# HV_power.net
KiCad netlist of a schematic drawn in Altium Designer
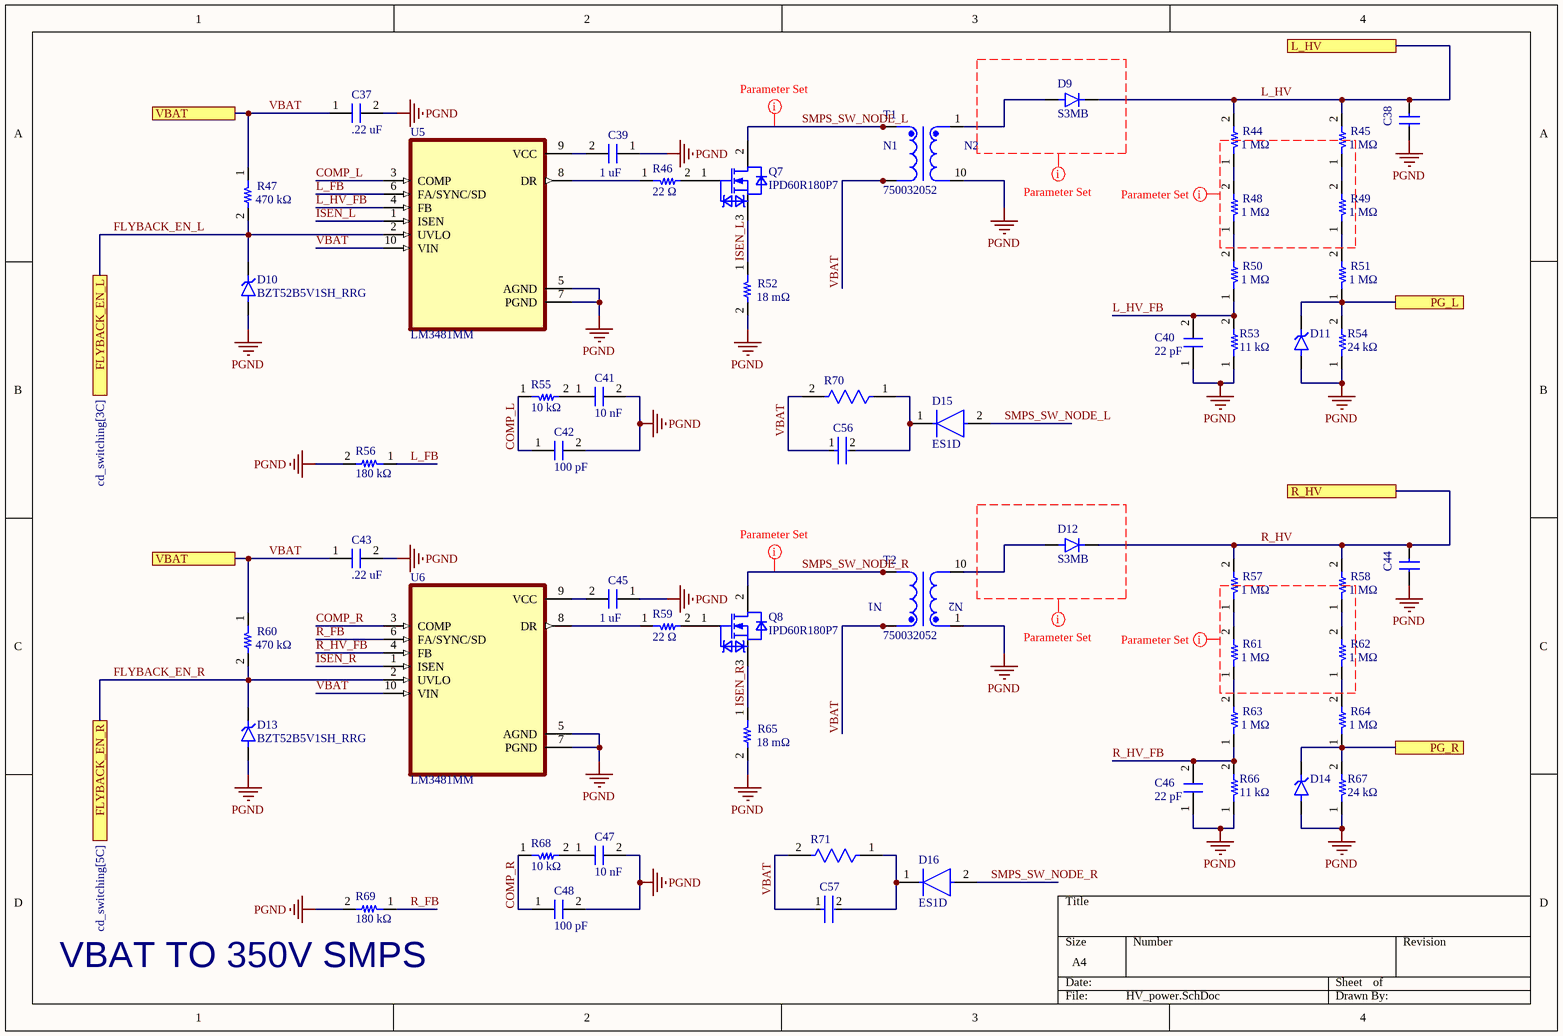
[diagram p0: HV_power.SchDoc]

(export (version "E")
  (design (tool "Eeschema 10.0.6"))
  (components
    (comp (ref "C37")
      (value ".22 uF")
      (footprint "0603_FP")
      (fields (field (name "Comment") "GRM21BR61C475KA88L"))
      (libsource (lib "RC_sch") (part "Capacitor_0603"))
    )
    (comp (ref "C38")
      (value "WCAP-FTBP_P10")
      (footprint "WCAP-FTBP_10X13X5.5X11(PXLXWXH)")
      (fields (field (name "MF") "Wurth Elektronik") (field (name "MP") "890283323005CS"))
      (libsource (lib "WCAP-FTBP_P10") (part "WCAP-FTBP_P10"))
    )
    (comp (ref "C39")
      (value "1 uF")
      (footprint "0603_FP")
      (fields (field (name "Comment") "Capacitor_0603"))
      (libsource (lib "RC_sch") (part "Capacitor_0603"))
    )
    (comp (ref "C40")
      (value "22 pF")
      (footprint "0603_FP")
      (fields (field (name "Comment") "Capacitor_0603"))
      (libsource (lib "RC_sch") (part "Capacitor_0603"))
    )
    (comp (ref "C41")
      (value "10 nF")
      (footprint "0603_FP")
      (fields (field (name "Comment") "Capacitor_0603"))
      (libsource (lib "RC_sch") (part "Capacitor_0603"))
    )
    (comp (ref "C42")
      (value "100 pF")
      (footprint "0603_FP")
      (fields (field (name "Comment") "Capacitor_0603"))
      (libsource (lib "RC_sch") (part "Capacitor_0603"))
    )
    (comp (ref "C43")
      (value ".22 uF")
      (footprint "0603_FP")
      (fields (field (name "Comment") "GRM21BR61C475KA88L"))
      (libsource (lib "RC_sch") (part "Capacitor_0603"))
    )
    (comp (ref "C44")
      (value "WCAP-FTBP_P10")
      (footprint "WCAP-FTBP_10X13X5.5X11(PXLXWXH)")
      (fields (field (name "MF") "Wurth Elektronik") (field (name "MP") "890283323005CS"))
      (libsource (lib "WCAP-FTBP_P10") (part "WCAP-FTBP_P10"))
    )
    (comp (ref "C45")
      (value "1 uF")
      (footprint "0603_FP")
      (fields (field (name "Comment") "Capacitor_0603"))
      (libsource (lib "RC_sch") (part "Capacitor_0603"))
    )
    (comp (ref "C46")
      (value "22 pF")
      (footprint "0603_FP")
      (fields (field (name "Comment") "Capacitor_0603"))
      (libsource (lib "RC_sch") (part "Capacitor_0603"))
    )
    (comp (ref "C47")
      (value "10 nF")
      (footprint "0603_FP")
      (fields (field (name "Comment") "Capacitor_0603"))
      (libsource (lib "RC_sch") (part "Capacitor_0603"))
    )
    (comp (ref "C48")
      (value "100 pF")
      (footprint "0603_FP")
      (fields (field (name "Comment") "Capacitor_0603"))
      (libsource (lib "RC_sch") (part "Capacitor_0603"))
    )
    (comp (ref "C56")
      (value "C1206C683K1RACAUTO")
      (footprint "FP-C1206C-EB-MFG")
      (description "C1206 68,000 pF X7R 10.00% 100 V")
      (fields
        (field (name "MANUFACTURER") "KEMET")
        (field (name "OCTOPART") "https://octopart.com/c1206c683k1racauto-kemet-89187447")
      )
      (libsource (lib "Altium Content Vault") (part "b4654b650e69147ec39a6b967a45e02"))
    )
    (comp (ref "C57")
      (value "C1206C683K1RACAUTO")
      (footprint "FP-C1206C-EB-MFG")
      (description "C1206 68,000 pF X7R 10.00% 100 V")
      (fields
        (field (name "MANUFACTURER") "KEMET")
        (field (name "OCTOPART") "https://octopart.com/c1206c683k1racauto-kemet-89187447")
      )
      (libsource (lib "Altium Content Vault") (part "b4654b650e69147ec39a6b967a45e02"))
    )
    (comp (ref "D9")
      (value "S3MB")
      (footprint "DIOM4336X265N")
      (description "3A, 1000V, Standard Recovery Rectifier")
      (fields (field (name "MF") "Taiwan Semiconductor"))
      (libsource (lib "S3MB") (part "S3MB"))
    )
    (comp (ref "D10")
      (value "BZT52B5V1SH_RRG")
      (footprint "DIO_BZT52B5V1SH_RRG")
      (description "SOD-323, 200mW, 2%, 5.1V, Zener Diode")
      (fields (field (name "MF") "Taiwan Semiconductor Corporation") (field (name "MP") "BZT52B5V1SH RRG"))
      (libsource (lib "BZT52B5V1SH_RRG") (part "BZT52B5V1SH_RRG"))
    )
    (comp (ref "D11")
      (value "BZT52B15SH_RRG")
      (footprint "DIO_BZT52B15SH_RRG")
      (description "SOD-323, 200mW, 2%, 15V, Zener Diode")
      (fields (field (name "MF") "Taiwan Semiconductor Corporation") (field (name "MP") "BZT52B15SH RRG"))
      (libsource (lib "BZT52B15SH_RRG") (part "BZT52B15SH_RRG"))
    )
    (comp (ref "D12")
      (value "S3MB")
      (footprint "DIOM4336X265N")
      (description "3A, 1000V, Standard Recovery Rectifier")
      (fields (field (name "MF") "Taiwan Semiconductor"))
      (libsource (lib "S3MB") (part "S3MB"))
    )
    (comp (ref "D13")
      (value "BZT52B5V1SH_RRG")
      (footprint "DIO_BZT52B5V1SH_RRG")
      (description "SOD-323, 200mW, 2%, 5.1V, Zener Diode")
      (fields (field (name "MF") "Taiwan Semiconductor Corporation") (field (name "MP") "BZT52B5V1SH RRG"))
      (libsource (lib "BZT52B5V1SH_RRG") (part "BZT52B5V1SH_RRG"))
    )
    (comp (ref "D14")
      (value "BZT52B15SH_RRG")
      (footprint "DIO_BZT52B15SH_RRG")
      (description "SOD-323, 200mW, 2%, 15V, Zener Diode")
      (fields (field (name "MF") "Taiwan Semiconductor Corporation") (field (name "MP") "BZT52B15SH RRG"))
      (libsource (lib "BZT52B15SH_RRG") (part "BZT52B15SH_RRG"))
    )
    (comp (ref "D15")
      (value "ES1D")
      (footprint "FP-403AE-MFG")
      (description "Diode Switching 200V 1A 2-Pin SMA T/R")
      (fields (field (name "MANUFACTURER") "ON Semi"))
      (libsource (lib "Altium Content Vault") (part "d7152d700b627762746794eb795d46e"))
    )
    (comp (ref "D16")
      (value "ES1D")
      (footprint "FP-403AE-MFG")
      (description "Diode Switching 200V 1A 2-Pin SMA T/R")
      (fields (field (name "MANUFACTURER") "ON Semi"))
      (libsource (lib "Altium Content Vault") (part "d7152d700b627762746794eb795d46e"))
    )
    (comp (ref "Q7")
      (value "IPD60R180P7")
      (footprint "DPAK228P987X240-3N")
      (fields (field (name "MANUFACTURER") "Infineon Technologies"))
      (libsource (lib "IPD60R180P7") (part "IPD60R180P7"))
    )
    (comp (ref "Q8")
      (value "IPD60R180P7")
      (footprint "DPAK228P987X240-3N")
      (fields (field (name "MANUFACTURER") "Infineon Technologies"))
      (libsource (lib "IPD60R180P7") (part "IPD60R180P7"))
    )
    (comp (ref "R44")
      (value "1 MΩ")
      (footprint "0805_FP")
      (fields (field (name "Comment") "R_0805"))
      (libsource (lib "0805_R") (part "R_0805"))
    )
    (comp (ref "R45")
      (value "1 MΩ")
      (footprint "0805_FP")
      (fields (field (name "Comment") "R_0805"))
      (libsource (lib "0805_R") (part "R_0805"))
    )
    (comp (ref "R46")
      (value "22 Ω")
      (footprint "0603_FP")
      (fields (field (name "Comment") "Resistor_0603"))
      (libsource (lib "RC_sch") (part "Resistor_0603"))
    )
    (comp (ref "R47")
      (value "470 kΩ")
      (footprint "0603_FP")
      (fields (field (name "Comment") "Resistor_0603"))
      (libsource (lib "RC_sch") (part "Resistor_0603"))
    )
    (comp (ref "R48")
      (value "1 MΩ")
      (footprint "0805_FP")
      (fields (field (name "Comment") "R_0805"))
      (libsource (lib "0805_R") (part "R_0805"))
    )
    (comp (ref "R49")
      (value "1 MΩ")
      (footprint "0805_FP")
      (fields (field (name "Comment") "R_0805"))
      (libsource (lib "0805_R") (part "R_0805"))
    )
    (comp (ref "R50")
      (value "1 MΩ")
      (footprint "0805_FP")
      (fields (field (name "Comment") "R_0805"))
      (libsource (lib "0805_R") (part "R_0805"))
    )
    (comp (ref "R51")
      (value "1 MΩ")
      (footprint "0805_FP")
      (fields (field (name "Comment") "R_0805"))
      (libsource (lib "0805_R") (part "R_0805"))
    )
    (comp (ref "R52")
      (value "18 mΩ")
      (footprint "2010_FP")
      (fields (field (name "Comment") "2010_res"))
      (libsource (lib "2010_R") (part "2010_res"))
    )
    (comp (ref "R53")
      (value "11 kΩ")
      (footprint "0805_FP")
      (fields (field (name "Comment") "R_0805"))
      (libsource (lib "0805_R") (part "R_0805"))
    )
    (comp (ref "R54")
      (value "24 kΩ")
      (footprint "0805_FP")
      (fields (field (name "Comment") "R_0805"))
      (libsource (lib "0805_R") (part "R_0805"))
    )
    (comp (ref "R55")
      (value "10 kΩ")
      (footprint "0603_FP")
      (fields (field (name "Comment") "Resistor_0603"))
      (libsource (lib "RC_sch") (part "Resistor_0603"))
    )
    (comp (ref "R56")
      (value "180 kΩ")
      (footprint "0603_FP")
      (fields (field (name "Comment") "Resistor_0603"))
      (libsource (lib "RC_sch") (part "Resistor_0603"))
    )
    (comp (ref "R57")
      (value "1 MΩ")
      (footprint "0805_FP")
      (fields (field (name "Comment") "R_0805"))
      (libsource (lib "0805_R") (part "R_0805"))
    )
    (comp (ref "R58")
      (value "1 MΩ")
      (footprint "0805_FP")
      (fields (field (name "Comment") "R_0805"))
      (libsource (lib "0805_R") (part "R_0805"))
    )
    (comp (ref "R59")
      (value "22 Ω")
      (footprint "0603_FP")
      (fields (field (name "Comment") "Resistor_0603"))
      (libsource (lib "RC_sch") (part "Resistor_0603"))
    )
    (comp (ref "R60")
      (value "470 kΩ")
      (footprint "0603_FP")
      (fields (field (name "Comment") "Resistor_0603"))
      (libsource (lib "RC_sch") (part "Resistor_0603"))
    )
    (comp (ref "R61")
      (value "1 MΩ")
      (footprint "0805_FP")
      (fields (field (name "Comment") "R_0805"))
      (libsource (lib "0805_R") (part "R_0805"))
    )
    (comp (ref "R62")
      (value "1 MΩ")
      (footprint "0805_FP")
      (fields (field (name "Comment") "R_0805"))
      (libsource (lib "0805_R") (part "R_0805"))
    )
    (comp (ref "R63")
      (value "1 MΩ")
      (footprint "0805_FP")
      (fields (field (name "Comment") "R_0805"))
      (libsource (lib "0805_R") (part "R_0805"))
    )
    (comp (ref "R64")
      (value "1 MΩ")
      (footprint "0805_FP")
      (fields (field (name "Comment") "R_0805"))
      (libsource (lib "0805_R") (part "R_0805"))
    )
    (comp (ref "R65")
      (value "18 mΩ")
      (footprint "2010_FP")
      (fields (field (name "Comment") "2010_res"))
      (libsource (lib "2010_R") (part "2010_res"))
    )
    (comp (ref "R66")
      (value "11 kΩ")
      (footprint "0805_FP")
      (fields (field (name "Comment") "R_0805"))
      (libsource (lib "0805_R") (part "R_0805"))
    )
    (comp (ref "R67")
      (value "24 kΩ")
      (footprint "0805_FP")
      (fields (field (name "Comment") "R_0805"))
      (libsource (lib "0805_R") (part "R_0805"))
    )
    (comp (ref "R68")
      (value "10 kΩ")
      (footprint "0603_FP")
      (fields (field (name "Comment") "Resistor_0603"))
      (libsource (lib "RC_sch") (part "Resistor_0603"))
    )
    (comp (ref "R69")
      (value "180 kΩ")
      (footprint "0603_FP")
      (fields (field (name "Comment") "Resistor_0603"))
      (libsource (lib "RC_sch") (part "Resistor_0603"))
    )
    (comp (ref "R70")
      (value "CRCW25121K80FKEG")
      (footprint "FP-CRCW2512-e3-MFG")
      (description "RES SMD 1.8K OHM 1% 1W 2512")
      (fields (field (name "TOLERANCE") "1%"))
      (libsource (lib "Altium Content Vault") (part "1029c3af85768c4190bb7ad29bc67b5"))
    )
    (comp (ref "R71")
      (value "CRCW25121K80FKEG")
      (footprint "FP-CRCW2512-e3-MFG")
      (description "RES SMD 1.8K OHM 1% 1W 2512")
      (fields (field (name "TOLERANCE") "1%"))
      (libsource (lib "Altium Content Vault") (part "1029c3af85768c4190bb7ad29bc67b5"))
    )
    (comp (ref "T1")
      (value "750032052")
      (footprint "WE-FB3751_EFD20")
      (fields (field (name "MF") "Wurth Electronics"))
      (libsource (lib "") (part "750032052_1"))
    )
    (comp (ref "T2")
      (value "750032052")
      (footprint "WE-FB3751_EFD20")
      (fields (field (name "MF") "Wurth Electronics"))
      (libsource (lib "750032052") (part "750032052"))
    )
    (comp (ref "U5")
      (value "LM3481MM")
      (footprint "SOP50P490X110-10N")
      (description "2.97V to 48V High-Efficiency Controller for Boost, SEPIC and Flyback")
      (fields (field (name "MF") "Texas Instruments") (field (name "MP") "LM3481MM/NOPB"))
      (libsource (lib "LM3481MM") (part "LM3481MM"))
    )
    (comp (ref "U6")
      (value "LM3481MM")
      (footprint "SOP50P490X110-10N")
      (description "2.97V to 48V High-Efficiency Controller for Boost, SEPIC and Flyback")
      (fields (field (name "MF") "Texas Instruments") (field (name "MP") "LM3481MM/NOPB"))
      (libsource (lib "LM3481MM") (part "LM3481MM"))
    )
  )
  (nets
    (net (code "1") (name "/COMP_L") (class "Default")
      (node (ref "C42") (pin "1") (pinfunction "1_1") (pintype "passive"))
      (node (ref "R55") (pin "1") (pinfunction "1_1") (pintype "passive"))
      (node (ref "U5") (pin "3") (pinfunction "COMP_3") (pintype "input"))
    )
    (net (code "2") (name "/COMP_R") (class "Default")
      (node (ref "C48") (pin "1") (pinfunction "1_1") (pintype "passive"))
      (node (ref "R68") (pin "1") (pinfunction "1_1") (pintype "passive"))
      (node (ref "U6") (pin "3") (pinfunction "COMP_3") (pintype "input"))
    )
    (net (code "3") (name "/FLYBACK_EN_L") (class "Default")
      (node (ref "D10") (pin "1") (pinfunction "K_1") (pintype "passive"))
      (node (ref "R47") (pin "2") (pinfunction "2_2") (pintype "passive"))
      (node (ref "U5") (pin "2") (pinfunction "UVLO_2") (pintype "input"))
    )
    (net (code "4") (name "/FLYBACK_EN_R") (class "Default")
      (node (ref "D13") (pin "1") (pinfunction "K_1") (pintype "passive"))
      (node (ref "R60") (pin "2") (pinfunction "2_2") (pintype "passive"))
      (node (ref "U6") (pin "2") (pinfunction "UVLO_2") (pintype "input"))
    )
    (net (code "5") (name "/ISEN_L") (class "Default")
      (node (ref "Q7") (pin "3") (pinfunction "SOURCE_3") (pintype "passive"))
      (node (ref "R52") (pin "1") (pinfunction "1_1") (pintype "passive"))
      (node (ref "U5") (pin "1") (pinfunction "ISEN_1") (pintype "input"))
    )
    (net (code "6") (name "/ISEN_R") (class "Default")
      (node (ref "Q8") (pin "3") (pinfunction "SOURCE_3") (pintype "passive"))
      (node (ref "R65") (pin "1") (pinfunction "1_1") (pintype "passive"))
      (node (ref "U6") (pin "1") (pinfunction "ISEN_1") (pintype "input"))
    )
    (net (code "7") (name "/L_FB") (class "Default")
      (node (ref "R56") (pin "1") (pinfunction "1_1") (pintype "passive"))
      (node (ref "U5") (pin "6") (pinfunction "FA/SYNC/SD_6") (pintype "input"))
    )
    (net (code "8") (name "/L_HV") (class "Default")
      (node (ref "C38") (pin "2") (pinfunction "2_2") (pintype "passive"))
      (node (ref "D9") (pin "C") (pinfunction "K_C") (pintype "passive"))
      (node (ref "R44") (pin "2") (pinfunction "2_2") (pintype "passive"))
      (node (ref "R45") (pin "2") (pinfunction "2_2") (pintype "passive"))
    )
    (net (code "9") (name "/L_HV_FB") (class "Default")
      (node (ref "C40") (pin "2") (pinfunction "2_2") (pintype "passive"))
      (node (ref "R50") (pin "1") (pinfunction "1_1") (pintype "passive"))
      (node (ref "R53") (pin "2") (pinfunction "2_2") (pintype "passive"))
      (node (ref "U5") (pin "4") (pinfunction "FB_4") (pintype "input"))
    )
    (net (code "10") (name "/PG_L") (class "Default")
      (node (ref "D11") (pin "1") (pinfunction "K_1") (pintype "passive"))
      (node (ref "R51") (pin "1") (pinfunction "1_1") (pintype "passive"))
      (node (ref "R54") (pin "2") (pinfunction "2_2") (pintype "passive"))
    )
    (net (code "11") (name "/PG_R") (class "Default")
      (node (ref "D14") (pin "1") (pinfunction "K_1") (pintype "passive"))
      (node (ref "R64") (pin "1") (pinfunction "1_1") (pintype "passive"))
      (node (ref "R67") (pin "2") (pinfunction "2_2") (pintype "passive"))
    )
    (net (code "12") (name "/R_FB") (class "Default")
      (node (ref "R69") (pin "1") (pinfunction "1_1") (pintype "passive"))
      (node (ref "U6") (pin "6") (pinfunction "FA/SYNC/SD_6") (pintype "input"))
    )
    (net (code "13") (name "/R_HV") (class "Default")
      (node (ref "C44") (pin "2") (pinfunction "2_2") (pintype "passive"))
      (node (ref "D12") (pin "C") (pinfunction "K_C") (pintype "passive"))
      (node (ref "R57") (pin "2") (pinfunction "2_2") (pintype "passive"))
      (node (ref "R58") (pin "2") (pinfunction "2_2") (pintype "passive"))
    )
    (net (code "14") (name "/R_HV_FB") (class "Default")
      (node (ref "C46") (pin "2") (pinfunction "2_2") (pintype "passive"))
      (node (ref "R63") (pin "1") (pinfunction "1_1") (pintype "passive"))
      (node (ref "R66") (pin "2") (pinfunction "2_2") (pintype "passive"))
      (node (ref "U6") (pin "4") (pinfunction "FB_4") (pintype "input"))
    )
    (net (code "15") (name "/SMPS_SW_NODE_L") (class "Default")
      (node (ref "D15") (pin "2") (pinfunction "A_2") (pintype "passive"))
      (node (ref "Q7") (pin "2") (pinfunction "DRAIN_2") (pintype "passive"))
      (node (ref "T1") (pin "6") (pinfunction "6+7_6") (pintype "passive"))
      (node (ref "T1") (pin "7") (pinfunction "6+7_7") (pintype "passive"))
    )
    (net (code "16") (name "/SMPS_SW_NODE_R") (class "Default")
      (node (ref "D16") (pin "2") (pinfunction "A_2") (pintype "passive"))
      (node (ref "Q8") (pin "2") (pinfunction "DRAIN_2") (pintype "passive"))
      (node (ref "T2") (pin "4") (pinfunction "4+5_4") (pintype "passive"))
      (node (ref "T2") (pin "5") (pinfunction "4+5_5") (pintype "passive"))
    )
    (net (code "17") (name "/VBAT") (class "Default")
      (node (ref "C37") (pin "1") (pinfunction "1_1") (pintype "passive"))
      (node (ref "C43") (pin "1") (pinfunction "1_1") (pintype "passive"))
      (node (ref "C56") (pin "1") (pinfunction "1_1") (pintype "passive"))
      (node (ref "C57") (pin "1") (pinfunction "1_1") (pintype "passive"))
      (node (ref "R47") (pin "1") (pinfunction "1_1") (pintype "passive"))
      (node (ref "R60") (pin "1") (pinfunction "1_1") (pintype "passive"))
      (node (ref "R70") (pin "2") (pinfunction "2_2") (pintype "passive"))
      (node (ref "R71") (pin "2") (pinfunction "2_2") (pintype "passive"))
      (node (ref "T1") (pin "4") (pinfunction "4+5_4") (pintype "passive"))
      (node (ref "T1") (pin "5") (pinfunction "4+5_5") (pintype "passive"))
      (node (ref "T2") (pin "6") (pinfunction "6+7_6") (pintype "passive"))
      (node (ref "T2") (pin "7") (pinfunction "6+7_7") (pintype "passive"))
      (node (ref "U5") (pin "10") (pinfunction "VIN_10") (pintype "input"))
      (node (ref "U6") (pin "10") (pinfunction "VIN_10") (pintype "input"))
    )
    (net (code "18") (name "Net-(C41-Pad1)") (class "Default")
      (node (ref "C41") (pin "1") (pinfunction "1_1") (pintype "passive"))
      (node (ref "R55") (pin "2") (pinfunction "2_2") (pintype "passive"))
    )
    (net (code "19") (name "Net-(C47-Pad1)") (class "Default")
      (node (ref "C47") (pin "1") (pinfunction "1_1") (pintype "passive"))
      (node (ref "R68") (pin "2") (pinfunction "2_2") (pintype "passive"))
    )
    (net (code "20") (name "Net-(D9-PadA)") (class "Default")
      (node (ref "D9") (pin "A") (pinfunction "A_A") (pintype "passive"))
      (node (ref "T1") (pin "1") (pinfunction "1_1") (pintype "passive"))
    )
    (net (code "21") (name "Net-(D12-PadA)") (class "Default")
      (node (ref "D12") (pin "A") (pinfunction "A_A") (pintype "passive"))
      (node (ref "T2") (pin "10") (pinfunction "10_10") (pintype "passive"))
    )
    (net (code "22") (name "Net-(D15-C)") (class "Default")
      (node (ref "C56") (pin "2") (pinfunction "2_2") (pintype "passive"))
      (node (ref "D15") (pin "1") (pinfunction "C_1") (pintype "passive"))
      (node (ref "R70") (pin "1") (pinfunction "1_1") (pintype "passive"))
    )
    (net (code "23") (name "Net-(D16-C)") (class "Default")
      (node (ref "C57") (pin "2") (pinfunction "2_2") (pintype "passive"))
      (node (ref "D16") (pin "1") (pinfunction "C_1") (pintype "passive"))
      (node (ref "R71") (pin "1") (pinfunction "1_1") (pintype "passive"))
    )
    (net (code "24") (name "Net-(Q7-GATE)") (class "Default")
      (node (ref "Q7") (pin "1") (pinfunction "GATE_1") (pintype "passive"))
      (node (ref "R46") (pin "2") (pinfunction "2_2") (pintype "passive"))
    )
    (net (code "25") (name "Net-(Q8-GATE)") (class "Default")
      (node (ref "Q8") (pin "1") (pinfunction "GATE_1") (pintype "passive"))
      (node (ref "R59") (pin "2") (pinfunction "2_2") (pintype "passive"))
    )
    (net (code "26") (name "Net-(R44-Pad1)") (class "Default")
      (node (ref "R44") (pin "1") (pinfunction "1_1") (pintype "passive"))
      (node (ref "R48") (pin "2") (pinfunction "2_2") (pintype "passive"))
    )
    (net (code "27") (name "Net-(R45-Pad1)") (class "Default")
      (node (ref "R45") (pin "1") (pinfunction "1_1") (pintype "passive"))
      (node (ref "R49") (pin "2") (pinfunction "2_2") (pintype "passive"))
    )
    (net (code "28") (name "Net-(R48-Pad1)") (class "Default")
      (node (ref "R48") (pin "1") (pinfunction "1_1") (pintype "passive"))
      (node (ref "R50") (pin "2") (pinfunction "2_2") (pintype "passive"))
    )
    (net (code "29") (name "Net-(R49-Pad1)") (class "Default")
      (node (ref "R49") (pin "1") (pinfunction "1_1") (pintype "passive"))
      (node (ref "R51") (pin "2") (pinfunction "2_2") (pintype "passive"))
    )
    (net (code "30") (name "Net-(R57-Pad1)") (class "Default")
      (node (ref "R57") (pin "1") (pinfunction "1_1") (pintype "passive"))
      (node (ref "R61") (pin "2") (pinfunction "2_2") (pintype "passive"))
    )
    (net (code "31") (name "Net-(R58-Pad1)") (class "Default")
      (node (ref "R58") (pin "1") (pinfunction "1_1") (pintype "passive"))
      (node (ref "R62") (pin "2") (pinfunction "2_2") (pintype "passive"))
    )
    (net (code "32") (name "Net-(R61-Pad1)") (class "Default")
      (node (ref "R61") (pin "1") (pinfunction "1_1") (pintype "passive"))
      (node (ref "R63") (pin "2") (pinfunction "2_2") (pintype "passive"))
    )
    (net (code "33") (name "Net-(R62-Pad1)") (class "Default")
      (node (ref "R62") (pin "1") (pinfunction "1_1") (pintype "passive"))
      (node (ref "R64") (pin "2") (pinfunction "2_2") (pintype "passive"))
    )
    (net (code "34") (name "Net-(U5-DR)") (class "Default")
      (node (ref "R46") (pin "1") (pinfunction "1_1") (pintype "passive"))
      (node (ref "U5") (pin "8") (pinfunction "DR_8") (pintype "output"))
    )
    (net (code "35") (name "Net-(U5-VCC)") (class "Default")
      (node (ref "C39") (pin "2") (pinfunction "2_2") (pintype "passive"))
      (node (ref "U5") (pin "9") (pinfunction "VCC_9") (pintype "power_in"))
    )
    (net (code "36") (name "Net-(U6-DR)") (class "Default")
      (node (ref "R59") (pin "1") (pinfunction "1_1") (pintype "passive"))
      (node (ref "U6") (pin "8") (pinfunction "DR_8") (pintype "output"))
    )
    (net (code "37") (name "Net-(U6-VCC)") (class "Default")
      (node (ref "C45") (pin "2") (pinfunction "2_2") (pintype "passive"))
      (node (ref "U6") (pin "9") (pinfunction "VCC_9") (pintype "power_in"))
    )
    (net (code "38") (name "PGND") (class "Default")
      (node (ref "C37") (pin "2") (pinfunction "2_2") (pintype "passive"))
      (node (ref "C38") (pin "1") (pinfunction "1_1") (pintype "passive"))
      (node (ref "C39") (pin "1") (pinfunction "1_1") (pintype "passive"))
      (node (ref "C40") (pin "1") (pinfunction "1_1") (pintype "passive"))
      (node (ref "C41") (pin "2") (pinfunction "2_2") (pintype "passive"))
      (node (ref "C42") (pin "2") (pinfunction "2_2") (pintype "passive"))
      (node (ref "C43") (pin "2") (pinfunction "2_2") (pintype "passive"))
      (node (ref "C44") (pin "1") (pinfunction "1_1") (pintype "passive"))
      (node (ref "C45") (pin "1") (pinfunction "1_1") (pintype "passive"))
      (node (ref "C46") (pin "1") (pinfunction "1_1") (pintype "passive"))
      (node (ref "C47") (pin "2") (pinfunction "2_2") (pintype "passive"))
      (node (ref "C48") (pin "2") (pinfunction "2_2") (pintype "passive"))
      (node (ref "D10") (pin "2") (pinfunction "A_2") (pintype "passive"))
      (node (ref "D11") (pin "2") (pinfunction "A_2") (pintype "passive"))
      (node (ref "D13") (pin "2") (pinfunction "A_2") (pintype "passive"))
      (node (ref "D14") (pin "2") (pinfunction "A_2") (pintype "passive"))
      (node (ref "R52") (pin "2") (pinfunction "2_2") (pintype "passive"))
      (node (ref "R53") (pin "1") (pinfunction "1_1") (pintype "passive"))
      (node (ref "R54") (pin "1") (pinfunction "1_1") (pintype "passive"))
      (node (ref "R56") (pin "2") (pinfunction "2_2") (pintype "passive"))
      (node (ref "R65") (pin "2") (pinfunction "2_2") (pintype "passive"))
      (node (ref "R66") (pin "1") (pinfunction "1_1") (pintype "passive"))
      (node (ref "R67") (pin "1") (pinfunction "1_1") (pintype "passive"))
      (node (ref "R69") (pin "2") (pinfunction "2_2") (pintype "passive"))
      (node (ref "T1") (pin "10") (pinfunction "10_10") (pintype "passive"))
      (node (ref "T2") (pin "1") (pinfunction "1_1") (pintype "passive"))
      (node (ref "U5") (pin "5") (pinfunction "AGND_5") (pintype "power_in"))
      (node (ref "U5") (pin "7") (pinfunction "PGND_7") (pintype "power_in"))
      (node (ref "U6") (pin "5") (pinfunction "AGND_5") (pintype "power_in"))
      (node (ref "U6") (pin "7") (pinfunction "PGND_7") (pintype "power_in"))
    )
  )
)
